# SIDEPANELV4.net
KiCad netlist of a schematic drawn in EAGLE
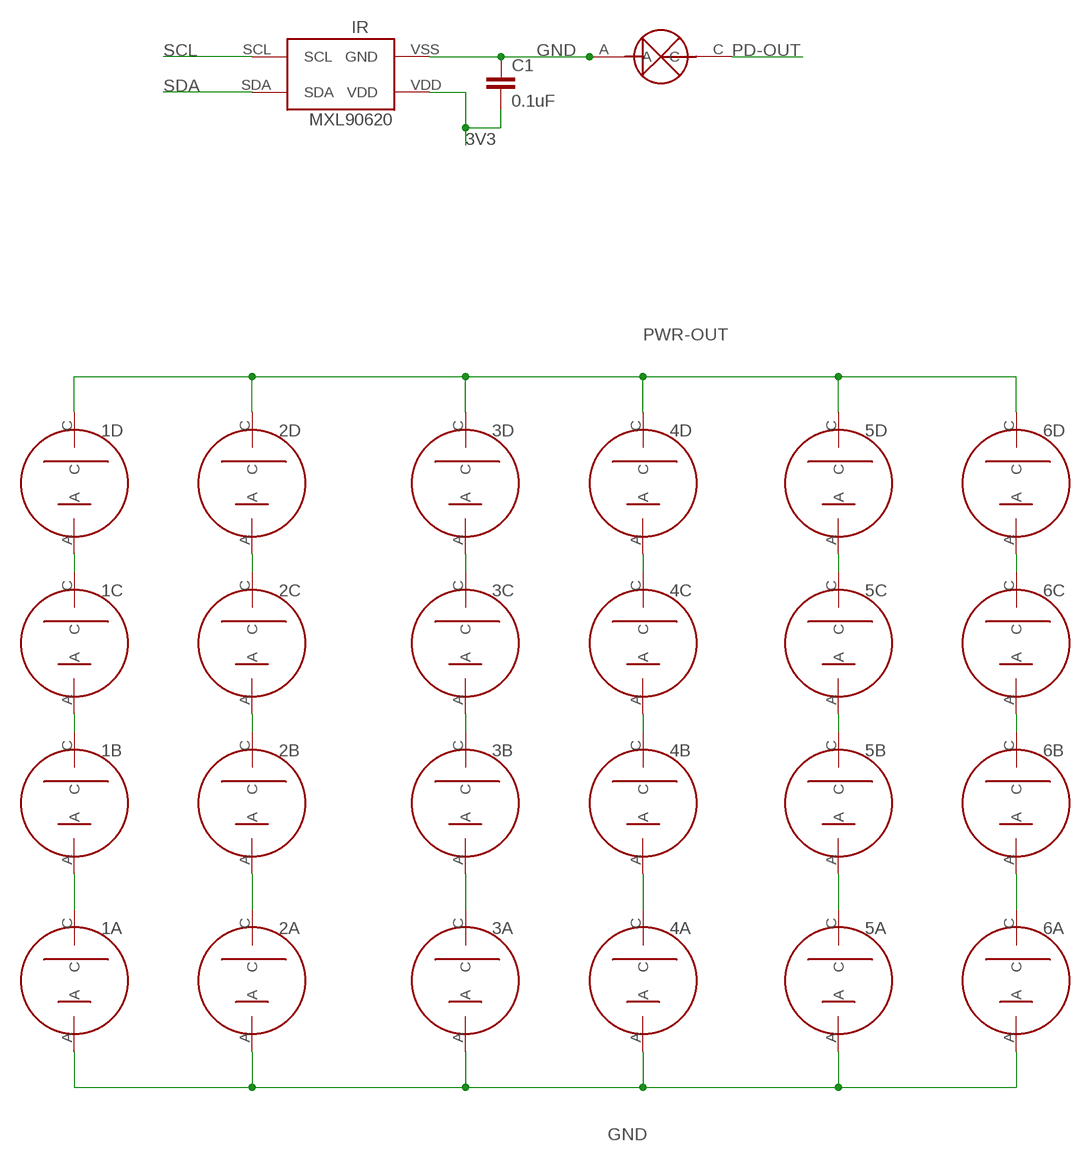
[diagram p0: schematic, sheet 1]

(export (version "E")
  (design (tool "Eeschema 10.0.6"))
  (components
    (comp (ref "1A")
      (value "NEWSOLARPANEL")
      (footprint "eagle-import:SOLARCELL2")
      (libsource (lib "eagle-import") (part "NEWSOLARPANEL"))
    )
    (comp (ref "1B")
      (value "NEWSOLARPANEL")
      (footprint "eagle-import:SOLARCELL2")
      (libsource (lib "eagle-import") (part "NEWSOLARPANEL"))
    )
    (comp (ref "1C")
      (value "NEWSOLARPANEL")
      (footprint "eagle-import:SOLARCELL2")
      (libsource (lib "eagle-import") (part "NEWSOLARPANEL"))
    )
    (comp (ref "1D")
      (value "NEWSOLARPANEL")
      (footprint "eagle-import:SOLARCELL2")
      (libsource (lib "eagle-import") (part "NEWSOLARPANEL"))
    )
    (comp (ref "2A")
      (value "NEWSOLARPANEL")
      (footprint "eagle-import:SOLARCELL2")
      (libsource (lib "eagle-import") (part "NEWSOLARPANEL"))
    )
    (comp (ref "2B")
      (value "NEWSOLARPANEL")
      (footprint "eagle-import:SOLARCELL2")
      (libsource (lib "eagle-import") (part "NEWSOLARPANEL"))
    )
    (comp (ref "2C")
      (value "NEWSOLARPANEL")
      (footprint "eagle-import:SOLARCELL2")
      (libsource (lib "eagle-import") (part "NEWSOLARPANEL"))
    )
    (comp (ref "2D")
      (value "NEWSOLARPANEL")
      (footprint "eagle-import:SOLARCELL2")
      (libsource (lib "eagle-import") (part "NEWSOLARPANEL"))
    )
    (comp (ref "3A")
      (value "NEWSOLARPANEL")
      (footprint "eagle-import:SOLARCELL2")
      (libsource (lib "eagle-import") (part "NEWSOLARPANEL"))
    )
    (comp (ref "3B")
      (value "NEWSOLARPANEL")
      (footprint "eagle-import:SOLARCELL2")
      (libsource (lib "eagle-import") (part "NEWSOLARPANEL"))
    )
    (comp (ref "3C")
      (value "NEWSOLARPANEL")
      (footprint "eagle-import:SOLARCELL2")
      (libsource (lib "eagle-import") (part "NEWSOLARPANEL"))
    )
    (comp (ref "3D")
      (value "NEWSOLARPANEL")
      (footprint "eagle-import:SOLARCELL2")
      (libsource (lib "eagle-import") (part "NEWSOLARPANEL"))
    )
    (comp (ref "4A")
      (value "NEWSOLARPANEL")
      (footprint "eagle-import:SOLARCELL2")
      (libsource (lib "eagle-import") (part "NEWSOLARPANEL"))
    )
    (comp (ref "4B")
      (value "NEWSOLARPANEL")
      (footprint "eagle-import:SOLARCELL2")
      (libsource (lib "eagle-import") (part "NEWSOLARPANEL"))
    )
    (comp (ref "4C")
      (value "NEWSOLARPANEL")
      (footprint "eagle-import:SOLARCELL2")
      (libsource (lib "eagle-import") (part "NEWSOLARPANEL"))
    )
    (comp (ref "4D")
      (value "NEWSOLARPANEL")
      (footprint "eagle-import:SOLARCELL2")
      (libsource (lib "eagle-import") (part "NEWSOLARPANEL"))
    )
    (comp (ref "5A")
      (value "NEWSOLARPANEL")
      (footprint "eagle-import:SOLARCELL2")
      (libsource (lib "eagle-import") (part "NEWSOLARPANEL"))
    )
    (comp (ref "5B")
      (value "NEWSOLARPANEL")
      (footprint "eagle-import:SOLARCELL2")
      (libsource (lib "eagle-import") (part "NEWSOLARPANEL"))
    )
    (comp (ref "5C")
      (value "NEWSOLARPANEL")
      (footprint "eagle-import:SOLARCELL2")
      (libsource (lib "eagle-import") (part "NEWSOLARPANEL"))
    )
    (comp (ref "5D")
      (value "NEWSOLARPANEL")
      (footprint "eagle-import:SOLARCELL2")
      (libsource (lib "eagle-import") (part "NEWSOLARPANEL"))
    )
    (comp (ref "6A")
      (value "NEWSOLARPANEL")
      (footprint "eagle-import:SOLARCELL2")
      (libsource (lib "eagle-import") (part "NEWSOLARPANEL"))
    )
    (comp (ref "6B")
      (value "NEWSOLARPANEL")
      (footprint "eagle-import:SOLARCELL2")
      (libsource (lib "eagle-import") (part "NEWSOLARPANEL"))
    )
    (comp (ref "6C")
      (value "NEWSOLARPANEL")
      (footprint "eagle-import:SOLARCELL2")
      (libsource (lib "eagle-import") (part "NEWSOLARPANEL"))
    )
    (comp (ref "6D")
      (value "NEWSOLARPANEL")
      (footprint "eagle-import:SOLARCELL2")
      (libsource (lib "eagle-import") (part "NEWSOLARPANEL"))
    )
    (comp (ref "C1")
      (value "0.1uF")
      (footprint "eagle-import:0805")
      (libsource (lib "eagle-import") (part "CAP0805"))
    )
    (comp (ref "IR")
      (value "MXL90620")
      (footprint "eagle-import:MXL90620")
      (libsource (lib "eagle-import") (part "MXL90620"))
    )
    (comp (ref "PD")
      (value "PHOTODETECTOR")
      (footprint "eagle-import:PHOTODECTORDEVICE2")
      (libsource (lib "eagle-import") (part "PHOTODETECTOR"))
    )
  )
  (nets
    (net (code "1") (name "/3V3") (class "Default")
      (node (ref "C1") (pin "2") (pinfunction "2_2") (pintype "passive"))
      (node (ref "IR") (pin "VDD") (pinfunction "VDD_VDD") (pintype "bidirectional"))
    )
    (net (code "2") (name "/GND") (class "Default")
      (node (ref "1A") (pin "A") (pinfunction "A_A") (pintype "bidirectional"))
      (node (ref "2A") (pin "A") (pinfunction "A_A") (pintype "bidirectional"))
      (node (ref "3A") (pin "A") (pinfunction "A_A") (pintype "bidirectional"))
      (node (ref "4A") (pin "A") (pinfunction "A_A") (pintype "bidirectional"))
      (node (ref "5A") (pin "A") (pinfunction "A_A") (pintype "bidirectional"))
      (node (ref "6A") (pin "A") (pinfunction "A_A") (pintype "bidirectional"))
      (node (ref "C1") (pin "1") (pinfunction "1_1") (pintype "passive"))
      (node (ref "IR") (pin "VSS") (pinfunction "GND_VSS") (pintype "bidirectional"))
      (node (ref "PD") (pin "A") (pinfunction "A_A") (pintype "bidirectional"))
    )
    (net (code "3") (name "/PD-OUT") (class "Default")
      (node (ref "PD") (pin "C") (pinfunction "C_C") (pintype "bidirectional"))
    )
    (net (code "4") (name "/PWR-OUT") (class "Default")
      (node (ref "1D") (pin "C") (pinfunction "C_C") (pintype "bidirectional"))
      (node (ref "2D") (pin "C") (pinfunction "C_C") (pintype "bidirectional"))
      (node (ref "3D") (pin "C") (pinfunction "C_C") (pintype "bidirectional"))
      (node (ref "4D") (pin "C") (pinfunction "C_C") (pintype "bidirectional"))
      (node (ref "5D") (pin "C") (pinfunction "C_C") (pintype "bidirectional"))
      (node (ref "6D") (pin "C") (pinfunction "C_C") (pintype "bidirectional"))
    )
    (net (code "5") (name "/SCL") (class "Default")
      (node (ref "IR") (pin "SCL") (pinfunction "SCL_SCL") (pintype "bidirectional"))
    )
    (net (code "6") (name "/SDA") (class "Default")
      (node (ref "IR") (pin "SDA") (pinfunction "SDA_SDA") (pintype "bidirectional"))
    )
    (net (code "7") (name "Net-(1A-PadC)") (class "Default")
      (node (ref "1A") (pin "C") (pinfunction "C_C") (pintype "bidirectional"))
      (node (ref "1B") (pin "A") (pinfunction "A_A") (pintype "bidirectional"))
    )
    (net (code "8") (name "Net-(1B-PadC)") (class "Default")
      (node (ref "1B") (pin "C") (pinfunction "C_C") (pintype "bidirectional"))
      (node (ref "1C") (pin "A") (pinfunction "A_A") (pintype "bidirectional"))
    )
    (net (code "9") (name "Net-(1C-PadC)") (class "Default")
      (node (ref "1C") (pin "C") (pinfunction "C_C") (pintype "bidirectional"))
      (node (ref "1D") (pin "A") (pinfunction "A_A") (pintype "bidirectional"))
    )
    (net (code "10") (name "Net-(2A-PadC)") (class "Default")
      (node (ref "2A") (pin "C") (pinfunction "C_C") (pintype "bidirectional"))
      (node (ref "2B") (pin "A") (pinfunction "A_A") (pintype "bidirectional"))
    )
    (net (code "11") (name "Net-(2B-PadC)") (class "Default")
      (node (ref "2B") (pin "C") (pinfunction "C_C") (pintype "bidirectional"))
      (node (ref "2C") (pin "A") (pinfunction "A_A") (pintype "bidirectional"))
    )
    (net (code "12") (name "Net-(2C-PadC)") (class "Default")
      (node (ref "2C") (pin "C") (pinfunction "C_C") (pintype "bidirectional"))
      (node (ref "2D") (pin "A") (pinfunction "A_A") (pintype "bidirectional"))
    )
    (net (code "13") (name "Net-(3A-PadC)") (class "Default")
      (node (ref "3A") (pin "C") (pinfunction "C_C") (pintype "bidirectional"))
      (node (ref "3B") (pin "A") (pinfunction "A_A") (pintype "bidirectional"))
    )
    (net (code "14") (name "Net-(3B-PadC)") (class "Default")
      (node (ref "3B") (pin "C") (pinfunction "C_C") (pintype "bidirectional"))
      (node (ref "3C") (pin "A") (pinfunction "A_A") (pintype "bidirectional"))
    )
    (net (code "15") (name "Net-(3C-PadC)") (class "Default")
      (node (ref "3C") (pin "C") (pinfunction "C_C") (pintype "bidirectional"))
      (node (ref "3D") (pin "A") (pinfunction "A_A") (pintype "bidirectional"))
    )
    (net (code "16") (name "Net-(4A-PadC)") (class "Default")
      (node (ref "4A") (pin "C") (pinfunction "C_C") (pintype "bidirectional"))
      (node (ref "4B") (pin "A") (pinfunction "A_A") (pintype "bidirectional"))
    )
    (net (code "17") (name "Net-(4B-PadC)") (class "Default")
      (node (ref "4B") (pin "C") (pinfunction "C_C") (pintype "bidirectional"))
      (node (ref "4C") (pin "A") (pinfunction "A_A") (pintype "bidirectional"))
    )
    (net (code "18") (name "Net-(4C-PadC)") (class "Default")
      (node (ref "4C") (pin "C") (pinfunction "C_C") (pintype "bidirectional"))
      (node (ref "4D") (pin "A") (pinfunction "A_A") (pintype "bidirectional"))
    )
    (net (code "19") (name "Net-(5A-PadC)") (class "Default")
      (node (ref "5A") (pin "C") (pinfunction "C_C") (pintype "bidirectional"))
      (node (ref "5B") (pin "A") (pinfunction "A_A") (pintype "bidirectional"))
    )
    (net (code "20") (name "Net-(5B-PadC)") (class "Default")
      (node (ref "5B") (pin "C") (pinfunction "C_C") (pintype "bidirectional"))
      (node (ref "5C") (pin "A") (pinfunction "A_A") (pintype "bidirectional"))
    )
    (net (code "21") (name "Net-(5C-PadC)") (class "Default")
      (node (ref "5C") (pin "C") (pinfunction "C_C") (pintype "bidirectional"))
      (node (ref "5D") (pin "A") (pinfunction "A_A") (pintype "bidirectional"))
    )
    (net (code "22") (name "Net-(6A-PadC)") (class "Default")
      (node (ref "6A") (pin "C") (pinfunction "C_C") (pintype "bidirectional"))
      (node (ref "6B") (pin "A") (pinfunction "A_A") (pintype "bidirectional"))
    )
    (net (code "23") (name "Net-(6B-PadC)") (class "Default")
      (node (ref "6B") (pin "C") (pinfunction "C_C") (pintype "bidirectional"))
      (node (ref "6C") (pin "A") (pinfunction "A_A") (pintype "bidirectional"))
    )
    (net (code "24") (name "Net-(6C-PadC)") (class "Default")
      (node (ref "6C") (pin "C") (pinfunction "C_C") (pintype "bidirectional"))
      (node (ref "6D") (pin "A") (pinfunction "A_A") (pintype "bidirectional"))
    )
  )
)
